# 03_DISCRETE_LNA.net
KiCad netlist of a schematic drawn in Altium Designer
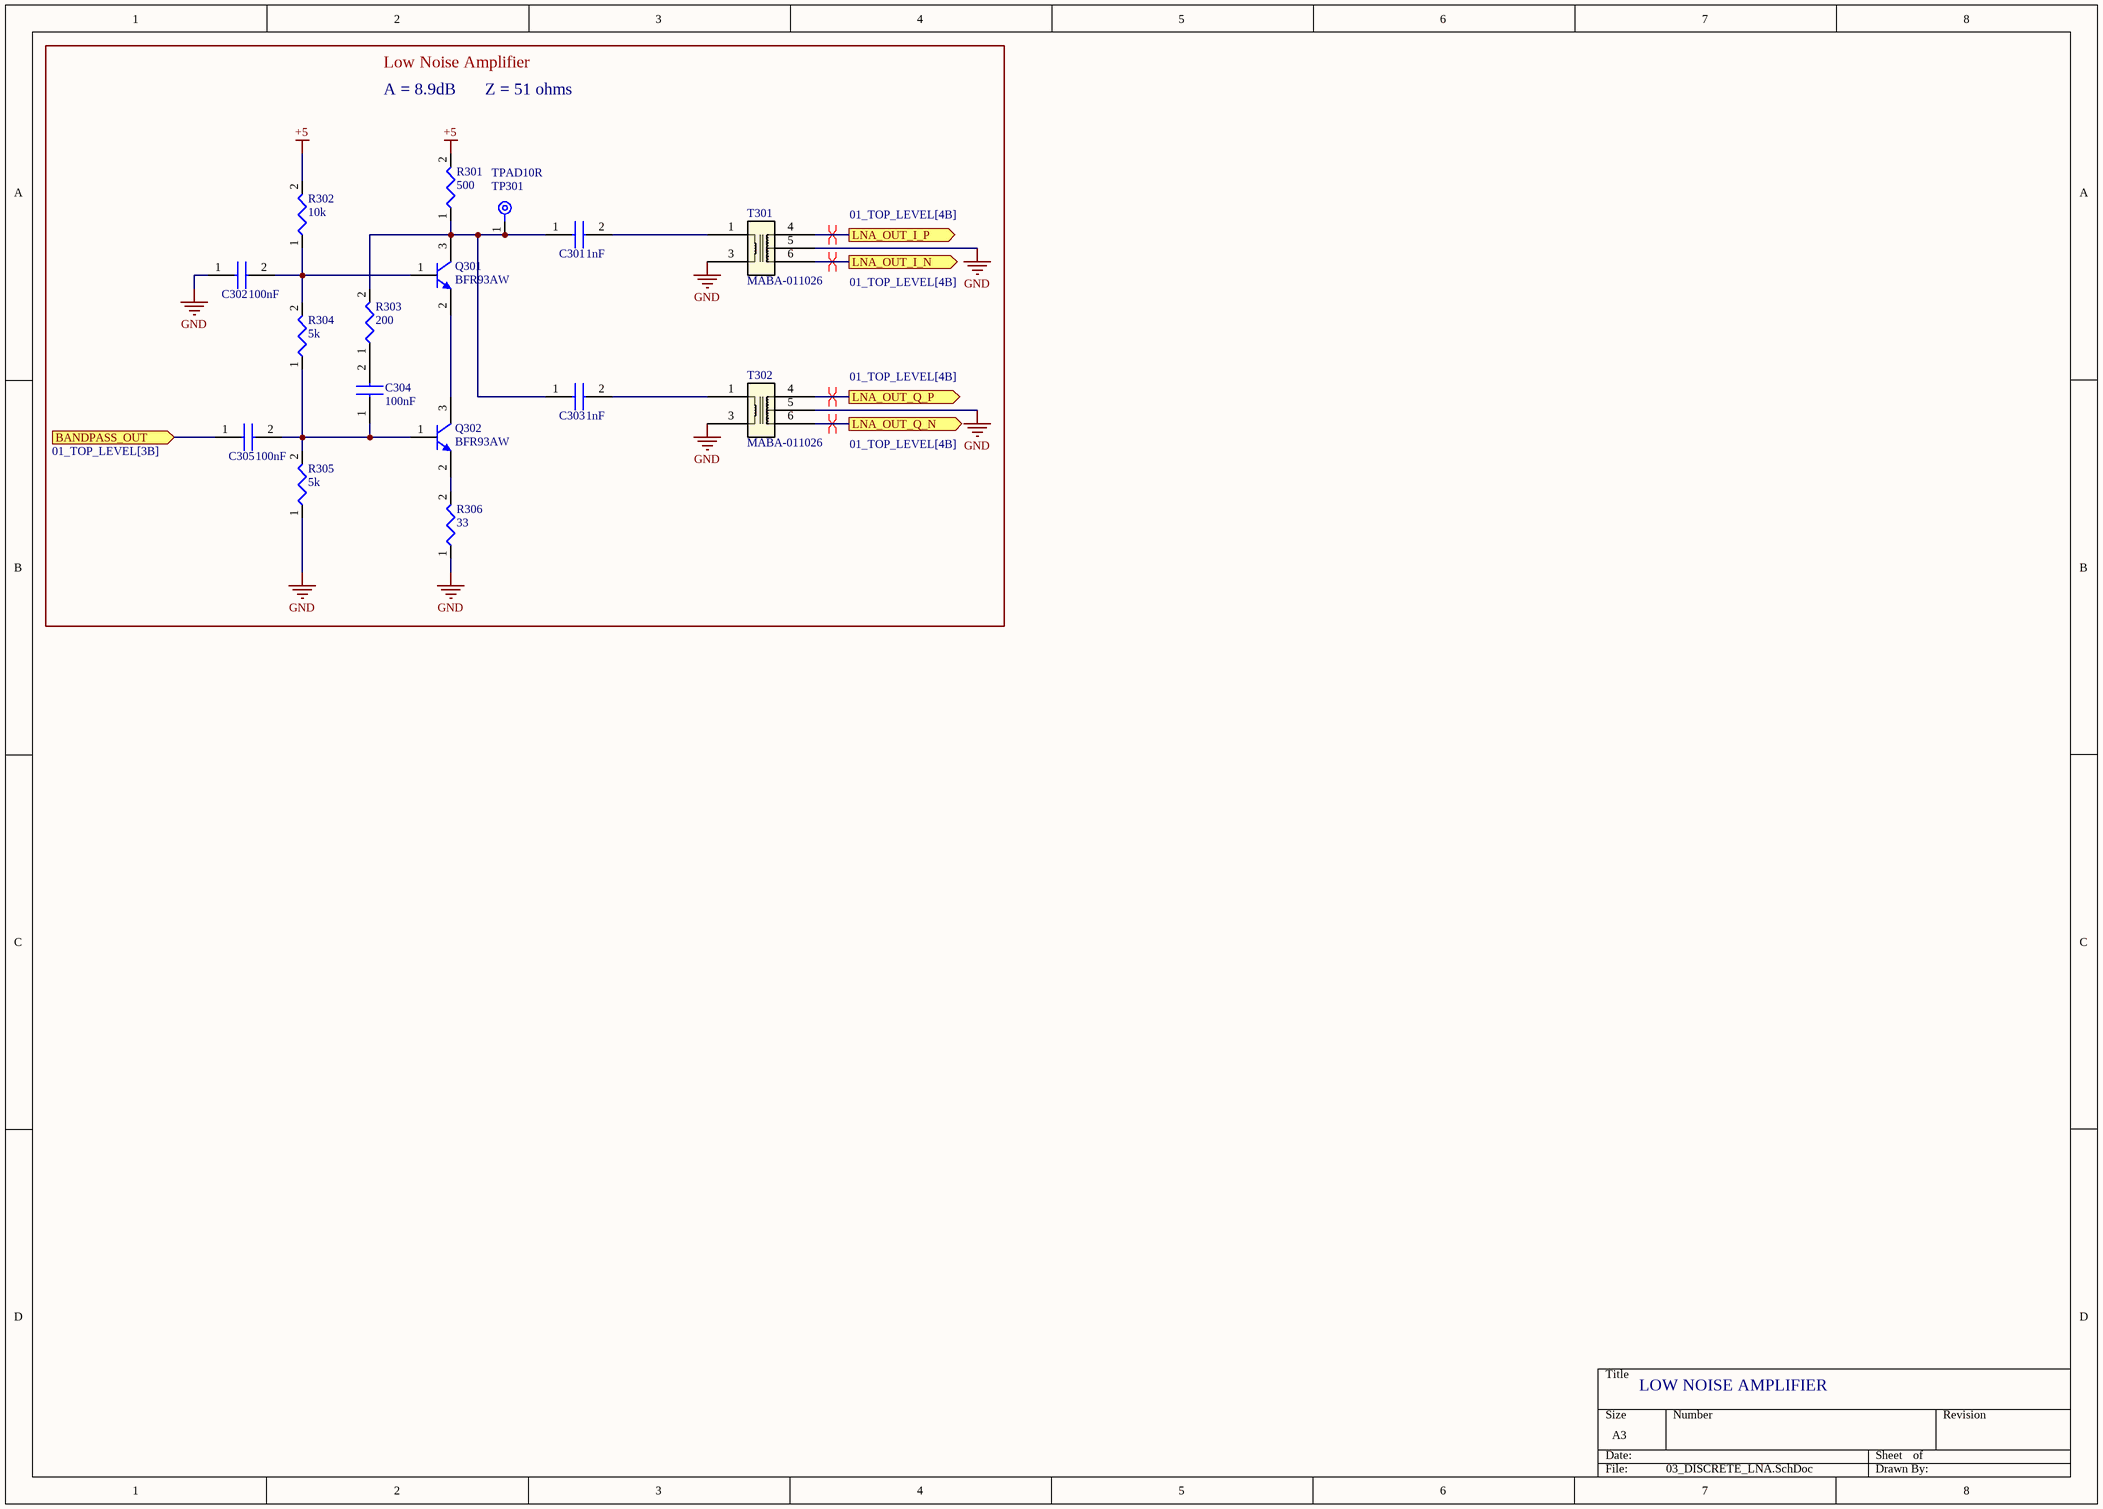
[diagram p0: 03_DISCRETE_LNA.SchDoc]

(export (version "E")
  (design (tool "Eeschema 10.0.6"))
  (components
    (comp (ref "C301")
      (value "1nF")
      (footprint "CAP_0805")
      (description "Capacitor SMD 0805")
      (libsource (lib "Passive_Components") (part "CAP_0805"))
    )
    (comp (ref "C302")
      (value "100nF")
      (footprint "CAP_0805")
      (description "Capacitor SMD 0805")
      (libsource (lib "Passive_Components") (part "CAP_0805"))
    )
    (comp (ref "C303")
      (value "1nF")
      (footprint "CAP_0805")
      (description "Capacitor SMD 0805")
      (libsource (lib "Passive_Components") (part "CAP_0805"))
    )
    (comp (ref "C304")
      (value "100nF")
      (footprint "CAP_0805")
      (description "Capacitor SMD 0805")
      (libsource (lib "Passive_Components") (part "CAP_0805"))
    )
    (comp (ref "C305")
      (value "100nF")
      (footprint "CAP_0805")
      (description "Capacitor SMD 0805")
      (libsource (lib "Passive_Components") (part "CAP_0805"))
    )
    (comp (ref "Q301")
      (value "BFR93AW")
      (footprint "INF-SOT323_M")
      (description "NPN Silicon RF Transistor, 12 V VCEO, 90 mA IC, 15.5 dB Gmax, SOT323, Green")
      (fields (field (name "MANUFACTURER") "Infineon"))
      (libsource (lib "Altium Content Vault") (part "INF-BFR93AW-3"))
    )
    (comp (ref "Q302")
      (value "BFR93AW")
      (footprint "INF-SOT323_M")
      (description "NPN Silicon RF Transistor, 12 V VCEO, 90 mA IC, 15.5 dB Gmax, SOT323, Green")
      (fields (field (name "MANUFACTURER") "Infineon"))
      (libsource (lib "Altium Content Vault") (part "INF-BFR93AW-3"))
    )
    (comp (ref "R301")
      (value "500")
      (footprint "RES_0805")
      (description "Resistor SMD 0805")
      (libsource (lib "Passive_Components") (part "RES_0805"))
    )
    (comp (ref "R302")
      (value "10k")
      (footprint "RES_0805")
      (description "Resistor SMD 0805")
      (libsource (lib "Passive_Components") (part "RES_0805"))
    )
    (comp (ref "R303")
      (value "200")
      (footprint "RES_0805")
      (description "Resistor SMD 0805")
      (libsource (lib "Passive_Components") (part "RES_0805"))
    )
    (comp (ref "R304")
      (value "5k")
      (footprint "RES_0805")
      (description "Resistor SMD 0805")
      (libsource (lib "Passive_Components") (part "RES_0805"))
    )
    (comp (ref "R305")
      (value "5k")
      (footprint "RES_0805")
      (description "Resistor SMD 0805")
      (libsource (lib "Passive_Components") (part "RES_0805"))
    )
    (comp (ref "R306")
      (value "33")
      (footprint "RES_0805")
      (description "Resistor SMD 0805")
      (libsource (lib "Passive_Components") (part "RES_0805"))
    )
    (comp (ref "T301")
      (value "MABA-011026")
      (footprint "MABA-011026_MCM")
      (description "RF Transformer")
      (fields (field (name "COPYRIGHT") "Copyright (C) 2025 Ultra Librarian. All rights reserved."))
      (libsource (lib "PASSIVE_COMPONENTS") (part "MABA-011026"))
    )
    (comp (ref "T302")
      (value "MABA-011026")
      (footprint "MABA-011026_MCM")
      (description "RF Transformer")
      (fields (field (name "COPYRIGHT") "Copyright (C) 2025 Ultra Librarian. All rights reserved."))
      (libsource (lib "PASSIVE_COMPONENTS") (part "MABA-011026"))
    )
    (comp (ref "TP301")
      (value "TPAD10R")
      (footprint "TEST_POINT")
      (description "Testpont Pad 10R")
      (libsource (lib "PASSIVE_COMPONENTS") (part "TEST_POINT"))
    )
  )
  (nets
    (net (code "1") (name "+5") (class "Default")
      (node (ref "R301") (pin "2") (pinfunction "2_2") (pintype "passive"))
      (node (ref "R302") (pin "2") (pinfunction "2_2") (pintype "passive"))
    )
    (net (code "2") (name "/BANDPASS_OUT") (class "Default")
      (node (ref "C305") (pin "1") (pinfunction "1_1") (pintype "passive"))
    )
    (net (code "3") (name "/LNA_OUT_I_N") (class "Default")
      (node (ref "T301") (pin "6") (pinfunction "6_6") (pintype "passive"))
    )
    (net (code "4") (name "/LNA_OUT_I_P") (class "Default")
      (node (ref "T301") (pin "4") (pinfunction "4_4") (pintype "passive"))
    )
    (net (code "5") (name "/LNA_OUT_Q_N") (class "Default")
      (node (ref "T302") (pin "6") (pinfunction "6_6") (pintype "passive"))
    )
    (net (code "6") (name "/LNA_OUT_Q_P") (class "Default")
      (node (ref "T302") (pin "4") (pinfunction "4_4") (pintype "passive"))
    )
    (net (code "7") (name "GND") (class "Default")
      (node (ref "C302") (pin "1") (pinfunction "1_1") (pintype "passive"))
      (node (ref "R305") (pin "1") (pinfunction "1_1") (pintype "passive"))
      (node (ref "R306") (pin "1") (pinfunction "1_1") (pintype "passive"))
      (node (ref "T301") (pin "3") (pinfunction "3_3") (pintype "passive"))
      (node (ref "T301") (pin "5") (pinfunction "5_5") (pintype "passive"))
      (node (ref "T302") (pin "3") (pinfunction "3_3") (pintype "passive"))
      (node (ref "T302") (pin "5") (pinfunction "5_5") (pintype "passive"))
    )
    (net (code "8") (name "Net-(C301-Pad2)") (class "Default")
      (node (ref "C301") (pin "2") (pinfunction "2_2") (pintype "passive"))
      (node (ref "T301") (pin "1") (pinfunction "1_1") (pintype "passive"))
    )
    (net (code "9") (name "Net-(C303-Pad2)") (class "Default")
      (node (ref "C303") (pin "2") (pinfunction "2_2") (pintype "passive"))
      (node (ref "T302") (pin "1") (pinfunction "1_1") (pintype "passive"))
    )
    (net (code "10") (name "Net-(C304-Pad2)") (class "Default")
      (node (ref "C304") (pin "2") (pinfunction "2_2") (pintype "passive"))
      (node (ref "R303") (pin "1") (pinfunction "1_1") (pintype "passive"))
    )
    (net (code "11") (name "Net-(Q301-B)") (class "Default")
      (node (ref "C302") (pin "2") (pinfunction "2_2") (pintype "passive"))
      (node (ref "Q301") (pin "1") (pinfunction "B_1") (pintype "passive"))
      (node (ref "R302") (pin "1") (pinfunction "1_1") (pintype "passive"))
      (node (ref "R304") (pin "2") (pinfunction "2_2") (pintype "passive"))
    )
    (net (code "12") (name "Net-(Q301-C)") (class "Default")
      (node (ref "C301") (pin "1") (pinfunction "1_1") (pintype "passive"))
      (node (ref "C303") (pin "1") (pinfunction "1_1") (pintype "passive"))
      (node (ref "Q301") (pin "3") (pinfunction "C_3") (pintype "passive"))
      (node (ref "R301") (pin "1") (pinfunction "1_1") (pintype "passive"))
      (node (ref "R303") (pin "2") (pinfunction "2_2") (pintype "passive"))
      (node (ref "TP301") (pin "1") (pinfunction "1_1") (pintype "passive"))
    )
    (net (code "13") (name "Net-(Q301-E)") (class "Default")
      (node (ref "Q301") (pin "2") (pinfunction "E_2") (pintype "passive"))
      (node (ref "Q302") (pin "3") (pinfunction "C_3") (pintype "passive"))
    )
    (net (code "14") (name "Net-(Q302-B)") (class "Default")
      (node (ref "C304") (pin "1") (pinfunction "1_1") (pintype "passive"))
      (node (ref "C305") (pin "2") (pinfunction "2_2") (pintype "passive"))
      (node (ref "Q302") (pin "1") (pinfunction "B_1") (pintype "passive"))
      (node (ref "R304") (pin "1") (pinfunction "1_1") (pintype "passive"))
      (node (ref "R305") (pin "2") (pinfunction "2_2") (pintype "passive"))
    )
    (net (code "15") (name "Net-(Q302-E)") (class "Default")
      (node (ref "Q302") (pin "2") (pinfunction "E_2") (pintype "passive"))
      (node (ref "R306") (pin "2") (pinfunction "2_2") (pintype "passive"))
    )
  )
)
